# RY835AI_Stratux.net
KiCad netlist of a schematic drawn in EAGLE
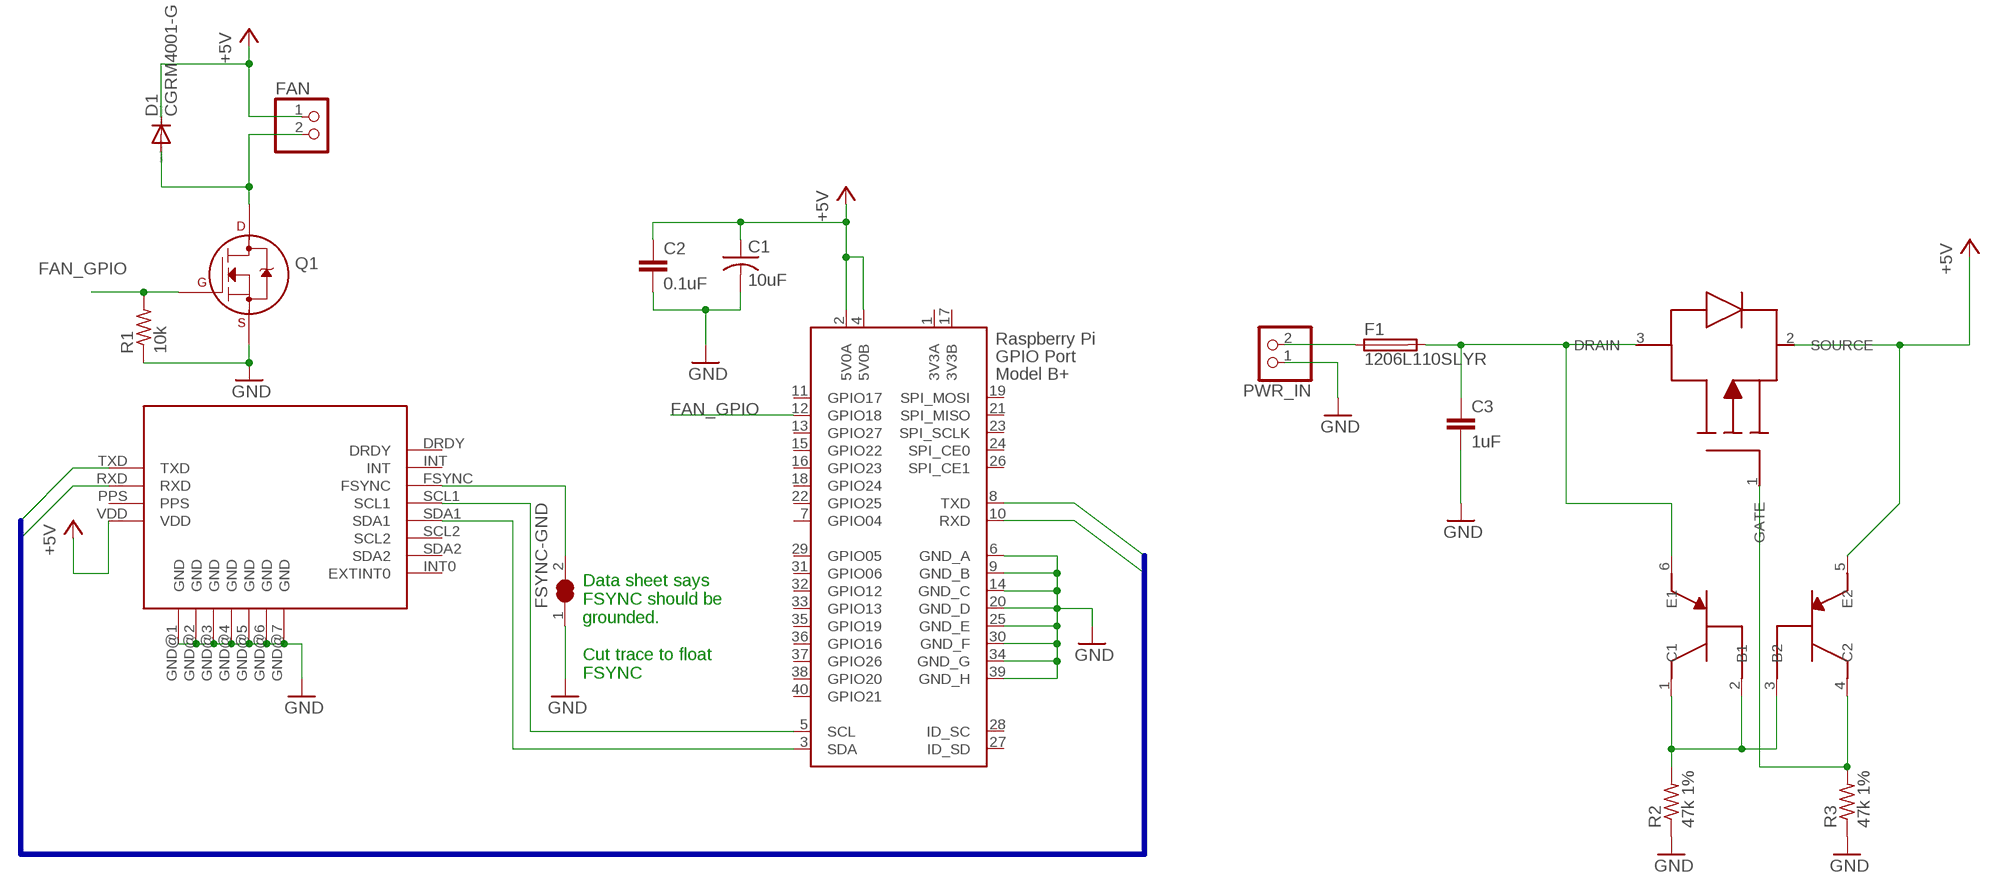
[diagram p0: schematic, sheet 1]

(export (version "E")
  (design (tool "Eeschema 10.0.6"))
  (components
    (comp (ref "C1")
      (value "10uF")
      (footprint "eagle-import:C0805")
      (libsource (lib "eagle-import") (part "C-USC0805"))
    )
    (comp (ref "C2")
      (value "0.1uF")
      (footprint "eagle-import:C0805")
      (libsource (lib "eagle-import") (part "C-EUC0805"))
    )
    (comp (ref "C3")
      (value "1uF")
      (footprint "eagle-import:C0805")
      (libsource (lib "eagle-import") (part "C-EUC0805"))
    )
    (comp (ref "D1")
      (value "CGRM4001-G")
      (footprint "eagle-import:SOD-123_MINI-SMA")
      (libsource (lib "eagle-import") (part "CGRM400-G1"))
    )
    (comp (ref "F1")
      (value "1206L110SLYR")
      (footprint "eagle-import:R1206")
      (libsource (lib "eagle-import") (part "FUSE"))
    )
    (comp (ref "FAN")
      (value "PINHD-1X2")
      (footprint "eagle-import:1X02")
      (libsource (lib "eagle-import") (part "PINHD-1X2"))
    )
    (comp (ref "FSYNC-GND")
      (value "CUTJUMPER")
      (footprint "eagle-import:R1206-CUTJUMPER")
      (libsource (lib "eagle-import") (part "CUTJUMPER"))
    )
    (comp (ref "PWR_IN")
      (value "PINHD-1X2")
      (footprint "eagle-import:1X02")
      (libsource (lib "eagle-import") (part "PINHD-1X2"))
    )
    (comp (ref "Q1")
      (value "2N7000_SOT23")
      (footprint "eagle-import:SOT-23")
      (libsource (lib "eagle-import") (part "2N700_SOT230"))
    )
    (comp (ref "R1")
      (value "10k")
      (footprint "eagle-import:R0805")
      (libsource (lib "eagle-import") (part "R-US_R0805"))
    )
    (comp (ref "R2")
      (value "47k 1%")
      (footprint "eagle-import:R0805")
      (libsource (lib "eagle-import") (part "R-US_R0805"))
    )
    (comp (ref "R3")
      (value "47k 1%")
      (footprint "eagle-import:R0805")
      (libsource (lib "eagle-import") (part "R-US_R0805"))
    )
    (comp (ref "U$1")
      (value "RY835AI")
      (footprint "eagle-import:RY835AI")
      (libsource (lib "eagle-import") (part "RY835AI"))
    )
    (comp (ref "U$2")
      (value "DMG2305UX")
      (footprint "eagle-import:SOT23")
      (libsource (lib "eagle-import") (part "DMG2305UX"))
    )
    (comp (ref "U$3")
      (value "DMMT5401")
      (footprint "eagle-import:SOT26")
      (libsource (lib "eagle-import") (part "DMMT5401"))
    )
    (comp (ref "X2")
      (value "RASPI_BOARD_B+#_HD")
      (footprint "eagle-import:RASPI_BOARD_B+HAT_DF")
      (libsource (lib "eagle-import") (part "RASPI_BOARD_B+#_HD"))
    )
  )
  (nets
    (net (code "1") (name "+5V") (class "Default")
      (node (ref "C1") (pin "1") (pinfunction "1_1") (pintype "passive"))
      (node (ref "C2") (pin "1") (pinfunction "1_1") (pintype "passive"))
      (node (ref "D1") (pin "C") (pinfunction "C_C") (pintype "passive"))
      (node (ref "FAN") (pin "1") (pinfunction "1_1") (pintype "passive"))
      (node (ref "U$1") (pin "VDD") (pinfunction "VDD_VDD") (pintype "power_in"))
      (node (ref "U$2") (pin "2") (pinfunction "SOURCE_2") (pintype "bidirectional"))
      (node (ref "U$3") (pin "5") (pinfunction "E2_5") (pintype "bidirectional"))
      (node (ref "X2") (pin "2") (pinfunction "5V0A_2") (pintype "power_in"))
      (node (ref "X2") (pin "4") (pinfunction "5V0B_4") (pintype "power_in"))
    )
    (net (code "2") (name "/3V3A") (class "Default")
      (node (ref "X2") (pin "1") (pinfunction "3V3A_1") (pintype "power_in"))
    )
    (net (code "3") (name "/3V3B") (class "Default")
      (node (ref "X2") (pin "17") (pinfunction "3V3B_17") (pintype "power_in"))
    )
    (net (code "4") (name "/FAN_GPIO") (class "Default")
      (node (ref "Q1") (pin "1") (pinfunction "G_1") (pintype "tri_state"))
      (node (ref "R1") (pin "2") (pinfunction "2_2") (pintype "passive"))
      (node (ref "X2") (pin "12") (pinfunction "GPIO18_12") (pintype "bidirectional"))
    )
    (net (code "5") (name "/RXTX_BUS0") (class "Default")
      (node (ref "U$1") (pin "RXD") (pinfunction "RXD_RXD") (pintype "input"))
      (node (ref "X2") (pin "8") (pinfunction "TXD_8") (pintype "bidirectional"))
    )
    (net (code "6") (name "/RXTX_BUS1") (class "Default")
      (node (ref "U$1") (pin "TXD") (pinfunction "TXD_TXD") (pintype "output"))
      (node (ref "X2") (pin "10") (pinfunction "RXD_10") (pintype "bidirectional"))
    )
    (net (code "7") (name "GND") (class "Default")
      (node (ref "C1") (pin "2") (pinfunction "2_2") (pintype "passive"))
      (node (ref "C2") (pin "2") (pinfunction "2_2") (pintype "passive"))
      (node (ref "C3") (pin "2") (pinfunction "2_2") (pintype "passive"))
      (node (ref "FSYNC-GND") (pin "1") (pinfunction "1_1") (pintype "passive"))
      (node (ref "PWR_IN") (pin "1") (pinfunction "1_1") (pintype "passive"))
      (node (ref "Q1") (pin "2") (pinfunction "S_2") (pintype "bidirectional"))
      (node (ref "R1") (pin "1") (pinfunction "1_1") (pintype "passive"))
      (node (ref "R2") (pin "1") (pinfunction "1_1") (pintype "passive"))
      (node (ref "R3") (pin "1") (pinfunction "1_1") (pintype "passive"))
      (node (ref "U$1") (pin "GND@1") (pinfunction "GND_GND@1") (pintype "power_in"))
      (node (ref "U$1") (pin "GND@2") (pinfunction "GND_GND@2") (pintype "power_in"))
      (node (ref "U$1") (pin "GND@3") (pinfunction "GND_GND@3") (pintype "power_in"))
      (node (ref "U$1") (pin "GND@4") (pinfunction "GND_GND@4") (pintype "power_in"))
      (node (ref "U$1") (pin "GND@5") (pinfunction "GND_GND@5") (pintype "power_in"))
      (node (ref "U$1") (pin "GND@6") (pinfunction "GND_GND@6") (pintype "power_in"))
      (node (ref "U$1") (pin "GND@7") (pinfunction "GND_GND@7") (pintype "power_in"))
      (node (ref "X2") (pin "14") (pinfunction "GND_C_14") (pintype "power_in"))
      (node (ref "X2") (pin "20") (pinfunction "GND_D_20") (pintype "power_in"))
      (node (ref "X2") (pin "25") (pinfunction "GND_E_25") (pintype "power_in"))
      (node (ref "X2") (pin "30") (pinfunction "GND_F_30") (pintype "power_in"))
      (node (ref "X2") (pin "34") (pinfunction "GND_G_34") (pintype "power_in"))
      (node (ref "X2") (pin "39") (pinfunction "GND_H_39") (pintype "power_in"))
      (node (ref "X2") (pin "6") (pinfunction "GND_A_6") (pintype "power_in"))
      (node (ref "X2") (pin "9") (pinfunction "GND_B_9") (pintype "power_in"))
    )
    (net (code "8") (name "Net-(F1-Pad1)") (class "Default")
      (node (ref "F1") (pin "1") (pinfunction "1_1") (pintype "passive"))
      (node (ref "PWR_IN") (pin "2") (pinfunction "2_2") (pintype "passive"))
    )
    (net (code "9") (name "Net-(FSYNC-GND-Pad2)") (class "Default")
      (node (ref "FSYNC-GND") (pin "2") (pinfunction "2_2") (pintype "passive"))
      (node (ref "U$1") (pin "FSYNC") (pinfunction "FSYNC_FSYNC") (pintype "input"))
    )
    (net (code "10") (name "Net-(Q1-D)") (class "Default")
      (node (ref "D1") (pin "A") (pinfunction "A_A") (pintype "passive"))
      (node (ref "FAN") (pin "2") (pinfunction "2_2") (pintype "passive"))
      (node (ref "Q1") (pin "3") (pinfunction "D_3") (pintype "bidirectional"))
    )
    (net (code "11") (name "Net-(U$2-DRAIN)") (class "Default")
      (node (ref "C3") (pin "1") (pinfunction "1_1") (pintype "passive"))
      (node (ref "F1") (pin "2") (pinfunction "2_2") (pintype "passive"))
      (node (ref "U$2") (pin "3") (pinfunction "DRAIN_3") (pintype "bidirectional"))
      (node (ref "U$3") (pin "6") (pinfunction "E1_6") (pintype "bidirectional"))
    )
    (net (code "12") (name "Net-(U$2-GATE)") (class "Default")
      (node (ref "R3") (pin "2") (pinfunction "2_2") (pintype "passive"))
      (node (ref "U$2") (pin "1") (pinfunction "GATE_1") (pintype "bidirectional"))
      (node (ref "U$3") (pin "4") (pinfunction "C2_4") (pintype "bidirectional"))
    )
    (net (code "13") (name "Net-(U$3-B1)") (class "Default")
      (node (ref "R2") (pin "2") (pinfunction "2_2") (pintype "passive"))
      (node (ref "U$3") (pin "1") (pinfunction "C1_1") (pintype "bidirectional"))
      (node (ref "U$3") (pin "2") (pinfunction "B1_2") (pintype "bidirectional"))
      (node (ref "U$3") (pin "3") (pinfunction "B2_3") (pintype "bidirectional"))
    )
    (net (code "14") (name "Net-(X2-SCL)") (class "Default")
      (node (ref "U$1") (pin "SCL1") (pinfunction "SCL1_SCL1") (pintype "bidirectional"))
      (node (ref "X2") (pin "5") (pinfunction "SCL_5") (pintype "bidirectional"))
    )
    (net (code "15") (name "Net-(X2-SDA)") (class "Default")
      (node (ref "U$1") (pin "SDA1") (pinfunction "SDA1_SDA1") (pintype "bidirectional"))
      (node (ref "X2") (pin "3") (pinfunction "SDA_3") (pintype "bidirectional"))
    )
    (net (code "16") (name "unconnected-(U$1-EXTINT0-PadINT0)") (class "Default")
      (node (ref "U$1") (pin "INT0") (pinfunction "EXTINT0_INT0") (pintype "input"))
    )
    (net (code "17") (name "unconnected-(U$1-PadDRDY)") (class "Default")
      (node (ref "U$1") (pin "DRDY") (pinfunction "DRDY_DRDY") (pintype "output"))
    )
    (net (code "18") (name "unconnected-(U$1-PadINT)") (class "Default")
      (node (ref "U$1") (pin "INT") (pinfunction "INT_INT") (pintype "output"))
    )
    (net (code "19") (name "unconnected-(U$1-PadPPS)") (class "Default")
      (node (ref "U$1") (pin "PPS") (pinfunction "PPS_PPS") (pintype "output"))
    )
    (net (code "20") (name "unconnected-(U$1-PadSCL2)") (class "Default")
      (node (ref "U$1") (pin "SCL2") (pinfunction "SCL2_SCL2") (pintype "bidirectional"))
    )
    (net (code "21") (name "unconnected-(U$1-PadSDA2)") (class "Default")
      (node (ref "U$1") (pin "SDA2") (pinfunction "SDA2_SDA2") (pintype "bidirectional"))
    )
    (net (code "22") (name "unconnected-(X2-GPIO04-Pad7)") (class "Default")
      (node (ref "X2") (pin "7") (pinfunction "GPIO04_7") (pintype "bidirectional"))
    )
    (net (code "23") (name "unconnected-(X2-GPIO05-Pad29)") (class "Default")
      (node (ref "X2") (pin "29") (pinfunction "GPIO05_29") (pintype "no_connect"))
    )
    (net (code "24") (name "unconnected-(X2-GPIO06-Pad31)") (class "Default")
      (node (ref "X2") (pin "31") (pinfunction "GPIO06_31") (pintype "no_connect"))
    )
    (net (code "25") (name "unconnected-(X2-GPIO12-Pad32)") (class "Default")
      (node (ref "X2") (pin "32") (pinfunction "GPIO12_32") (pintype "no_connect"))
    )
    (net (code "26") (name "unconnected-(X2-GPIO13-Pad33)") (class "Default")
      (node (ref "X2") (pin "33") (pinfunction "GPIO13_33") (pintype "no_connect"))
    )
    (net (code "27") (name "unconnected-(X2-GPIO16-Pad36)") (class "Default")
      (node (ref "X2") (pin "36") (pinfunction "GPIO16_36") (pintype "no_connect"))
    )
    (net (code "28") (name "unconnected-(X2-GPIO17-Pad11)") (class "Default")
      (node (ref "X2") (pin "11") (pinfunction "GPIO17_11") (pintype "bidirectional"))
    )
    (net (code "29") (name "unconnected-(X2-GPIO19-Pad35)") (class "Default")
      (node (ref "X2") (pin "35") (pinfunction "GPIO19_35") (pintype "no_connect"))
    )
    (net (code "30") (name "unconnected-(X2-GPIO20-Pad38)") (class "Default")
      (node (ref "X2") (pin "38") (pinfunction "GPIO20_38") (pintype "no_connect"))
    )
    (net (code "31") (name "unconnected-(X2-GPIO21-Pad40)") (class "Default")
      (node (ref "X2") (pin "40") (pinfunction "GPIO21_40") (pintype "no_connect"))
    )
    (net (code "32") (name "unconnected-(X2-GPIO22-Pad15)") (class "Default")
      (node (ref "X2") (pin "15") (pinfunction "GPIO22_15") (pintype "bidirectional"))
    )
    (net (code "33") (name "unconnected-(X2-GPIO23-Pad16)") (class "Default")
      (node (ref "X2") (pin "16") (pinfunction "GPIO23_16") (pintype "bidirectional"))
    )
    (net (code "34") (name "unconnected-(X2-GPIO24-Pad18)") (class "Default")
      (node (ref "X2") (pin "18") (pinfunction "GPIO24_18") (pintype "bidirectional"))
    )
    (net (code "35") (name "unconnected-(X2-GPIO25-Pad22)") (class "Default")
      (node (ref "X2") (pin "22") (pinfunction "GPIO25_22") (pintype "bidirectional"))
    )
    (net (code "36") (name "unconnected-(X2-GPIO26-Pad37)") (class "Default")
      (node (ref "X2") (pin "37") (pinfunction "GPIO26_37") (pintype "no_connect"))
    )
    (net (code "37") (name "unconnected-(X2-GPIO27-Pad13)") (class "Default")
      (node (ref "X2") (pin "13") (pinfunction "GPIO27_13") (pintype "bidirectional"))
    )
    (net (code "38") (name "unconnected-(X2-ID_SC-Pad28)") (class "Default")
      (node (ref "X2") (pin "28") (pinfunction "ID_SC_28") (pintype "no_connect"))
    )
    (net (code "39") (name "unconnected-(X2-ID_SD-Pad27)") (class "Default")
      (node (ref "X2") (pin "27") (pinfunction "ID_SD_27") (pintype "no_connect"))
    )
    (net (code "40") (name "unconnected-(X2-SPI_CE0-Pad24)") (class "Default")
      (node (ref "X2") (pin "24") (pinfunction "SPI_CE0_24") (pintype "bidirectional"))
    )
    (net (code "41") (name "unconnected-(X2-SPI_CE1-Pad26)") (class "Default")
      (node (ref "X2") (pin "26") (pinfunction "SPI_CE1_26") (pintype "bidirectional"))
    )
    (net (code "42") (name "unconnected-(X2-SPI_MISO-Pad21)") (class "Default")
      (node (ref "X2") (pin "21") (pinfunction "SPI_MISO_21") (pintype "bidirectional"))
    )
    (net (code "43") (name "unconnected-(X2-SPI_MOSI-Pad19)") (class "Default")
      (node (ref "X2") (pin "19") (pinfunction "SPI_MOSI_19") (pintype "bidirectional"))
    )
    (net (code "44") (name "unconnected-(X2-SPI_SCLK-Pad23)") (class "Default")
      (node (ref "X2") (pin "23") (pinfunction "SPI_SCLK_23") (pintype "bidirectional"))
    )
  )
)
